# C2000_communications_dock.net
KiCad netlist of a schematic drawn in EAGLE
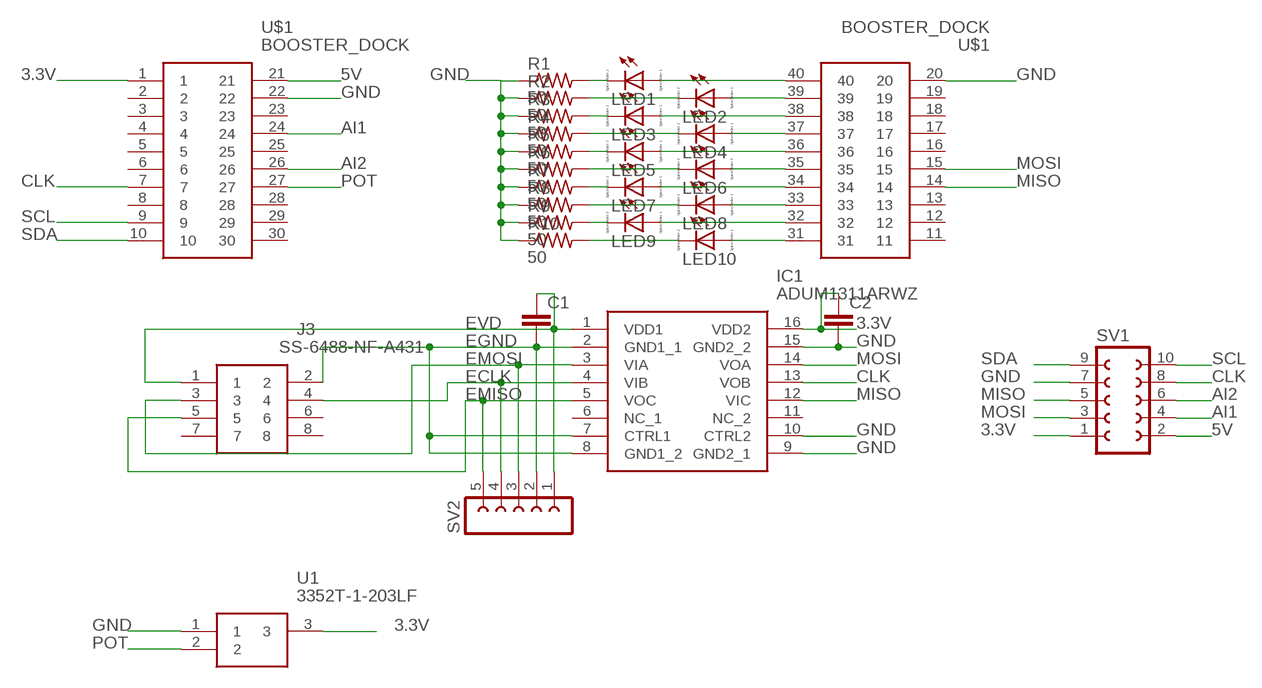
[diagram p0: schematic, sheet 1]

(export (version "E")
  (design (tool "Eeschema 10.0.6"))
  (components
    (comp (ref "C1")
      (value "C-EUC0603")
      (footprint "eagle-import:C0603")
      (libsource (lib "eagle-import") (part "C-EUC0603"))
    )
    (comp (ref "C2")
      (value "C-EUC0603")
      (footprint "eagle-import:C0603")
      (libsource (lib "eagle-import") (part "C-EUC0603"))
    )
    (comp (ref "IC1")
      (value "ADUM1311ARWZ")
      (footprint "eagle-import:SOIC127P1032X265-16N")
      (fields (field (name "MOUSER_PART_NUMBER") "584-ADUM1311ARWZ"))
      (libsource (lib "eagle-import") (part "ADUM1311ARWZ"))
    )
    (comp (ref "J3")
      (value "SS-6488-NF-A431")
      (footprint "eagle-import:SS6488NFA431")
      (fields (field (name "MOUSER_PART_NUMBER") "530-SS-6488-NF-A431"))
      (libsource (lib "eagle-import") (part "SS-6488-NF-A431"))
    )
    (comp (ref "LED1")
      (value "LED_ESML0603")
      (footprint "eagle-import:LED_SML0603")
      (libsource (lib "eagle-import") (part "LED_ESML0603"))
    )
    (comp (ref "LED2")
      (value "LED_ESML0603")
      (footprint "eagle-import:LED_SML0603")
      (libsource (lib "eagle-import") (part "LED_ESML0603"))
    )
    (comp (ref "LED3")
      (value "LED_ESML0603")
      (footprint "eagle-import:LED_SML0603")
      (libsource (lib "eagle-import") (part "LED_ESML0603"))
    )
    (comp (ref "LED4")
      (value "LED_ESML0603")
      (footprint "eagle-import:LED_SML0603")
      (libsource (lib "eagle-import") (part "LED_ESML0603"))
    )
    (comp (ref "LED5")
      (value "LED_ESML0603")
      (footprint "eagle-import:LED_SML0603")
      (libsource (lib "eagle-import") (part "LED_ESML0603"))
    )
    (comp (ref "LED6")
      (value "LED_ESML0603")
      (footprint "eagle-import:LED_SML0603")
      (libsource (lib "eagle-import") (part "LED_ESML0603"))
    )
    (comp (ref "LED7")
      (value "LED_ESML0603")
      (footprint "eagle-import:LED_SML0603")
      (libsource (lib "eagle-import") (part "LED_ESML0603"))
    )
    (comp (ref "LED8")
      (value "LED_ESML0603")
      (footprint "eagle-import:LED_SML0603")
      (libsource (lib "eagle-import") (part "LED_ESML0603"))
    )
    (comp (ref "LED9")
      (value "LED_ESML0603")
      (footprint "eagle-import:LED_SML0603")
      (libsource (lib "eagle-import") (part "LED_ESML0603"))
    )
    (comp (ref "LED10")
      (value "LED_ESML0603")
      (footprint "eagle-import:LED_SML0603")
      (libsource (lib "eagle-import") (part "LED_ESML0603"))
    )
    (comp (ref "R1")
      (value "50")
      (footprint "eagle-import:R0603")
      (libsource (lib "eagle-import") (part "R-US_R0603"))
    )
    (comp (ref "R2")
      (value "50")
      (footprint "eagle-import:R0603")
      (libsource (lib "eagle-import") (part "R-US_R0603"))
    )
    (comp (ref "R3")
      (value "50")
      (footprint "eagle-import:R0603")
      (libsource (lib "eagle-import") (part "R-US_R0603"))
    )
    (comp (ref "R4")
      (value "50")
      (footprint "eagle-import:R0603")
      (libsource (lib "eagle-import") (part "R-US_R0603"))
    )
    (comp (ref "R5")
      (value "50")
      (footprint "eagle-import:R0603")
      (libsource (lib "eagle-import") (part "R-US_R0603"))
    )
    (comp (ref "R6")
      (value "50")
      (footprint "eagle-import:R0603")
      (libsource (lib "eagle-import") (part "R-US_R0603"))
    )
    (comp (ref "R7")
      (value "50")
      (footprint "eagle-import:R0603")
      (libsource (lib "eagle-import") (part "R-US_R0603"))
    )
    (comp (ref "R8")
      (value "50")
      (footprint "eagle-import:R0603")
      (libsource (lib "eagle-import") (part "R-US_R0603"))
    )
    (comp (ref "R9")
      (value "50")
      (footprint "eagle-import:R0603")
      (libsource (lib "eagle-import") (part "R-US_R0603"))
    )
    (comp (ref "R10")
      (value "50")
      (footprint "eagle-import:R0603")
      (libsource (lib "eagle-import") (part "R-US_R0603"))
    )
    (comp (ref "SV1")
      (value "FE05-2")
      (footprint "eagle-import:FE05-2")
      (libsource (lib "eagle-import") (part "FE05-2"))
    )
    (comp (ref "SV2")
      (value "FE05-1")
      (footprint "eagle-import:FE05-1")
      (libsource (lib "eagle-import") (part "FE05-1"))
    )
    (comp (ref "U$1")
      (value "BOOSTER_DOCK")
      (footprint "eagle-import:BOOSTER_DOCK")
      (libsource (lib "eagle-import") (part "BOOSTER_DOCK"))
    )
    (comp (ref "U1")
      (value "3352T-1-203LF")
      (footprint "eagle-import:3352T-1-203LF")
      (fields (field (name "MOUSER_PART_NUMBER") "652-3352T-1-203LF"))
      (libsource (lib "eagle-import") (part "3352T-1-203LF"))
    )
  )
  (nets
    (net (code "1") (name "/3.3V") (class "Default")
      (node (ref "C2") (pin "1") (pinfunction "1_1") (pintype "passive"))
      (node (ref "IC1") (pin "16") (pinfunction "VDD2_16") (pintype "bidirectional"))
      (node (ref "SV1") (pin "1") (pinfunction "1_1") (pintype "passive"))
      (node (ref "U$1") (pin "1") (pinfunction "1_1") (pintype "bidirectional"))
      (node (ref "U1") (pin "3") (pinfunction "3_3") (pintype "bidirectional"))
    )
    (net (code "2") (name "/5V") (class "Default")
      (node (ref "SV1") (pin "2") (pinfunction "2_2") (pintype "passive"))
      (node (ref "U$1") (pin "21") (pinfunction "21_21") (pintype "bidirectional"))
    )
    (net (code "3") (name "/AI1") (class "Default")
      (node (ref "SV1") (pin "4") (pinfunction "4_4") (pintype "passive"))
      (node (ref "U$1") (pin "24") (pinfunction "24_24") (pintype "bidirectional"))
    )
    (net (code "4") (name "/AI2") (class "Default")
      (node (ref "SV1") (pin "6") (pinfunction "6_6") (pintype "passive"))
      (node (ref "U$1") (pin "26") (pinfunction "26_26") (pintype "bidirectional"))
    )
    (net (code "5") (name "/CLK") (class "Default")
      (node (ref "IC1") (pin "13") (pinfunction "VOB_13") (pintype "bidirectional"))
      (node (ref "SV1") (pin "8") (pinfunction "8_8") (pintype "passive"))
      (node (ref "U$1") (pin "7") (pinfunction "7_7") (pintype "bidirectional"))
    )
    (net (code "6") (name "/ECLK") (class "Default")
      (node (ref "IC1") (pin "4") (pinfunction "VIB_4") (pintype "bidirectional"))
      (node (ref "J3") (pin "4") (pinfunction "4_4") (pintype "bidirectional"))
      (node (ref "SV2") (pin "4") (pinfunction "4_4") (pintype "passive"))
    )
    (net (code "7") (name "/EGND") (class "Default")
      (node (ref "C1") (pin "2") (pinfunction "2_2") (pintype "passive"))
      (node (ref "IC1") (pin "2") (pinfunction "GND1_1_2") (pintype "bidirectional"))
      (node (ref "IC1") (pin "7") (pinfunction "CTRL1_7") (pintype "bidirectional"))
      (node (ref "IC1") (pin "8") (pinfunction "GND1_2_8") (pintype "bidirectional"))
      (node (ref "J3") (pin "2") (pinfunction "2_2") (pintype "bidirectional"))
      (node (ref "SV2") (pin "2") (pinfunction "2_2") (pintype "passive"))
    )
    (net (code "8") (name "/EMISO") (class "Default")
      (node (ref "IC1") (pin "5") (pinfunction "VOC_5") (pintype "bidirectional"))
      (node (ref "J3") (pin "5") (pinfunction "5_5") (pintype "bidirectional"))
      (node (ref "SV2") (pin "5") (pinfunction "5_5") (pintype "passive"))
    )
    (net (code "9") (name "/EMOSI") (class "Default")
      (node (ref "IC1") (pin "3") (pinfunction "VIA_3") (pintype "bidirectional"))
      (node (ref "J3") (pin "3") (pinfunction "3_3") (pintype "bidirectional"))
      (node (ref "SV2") (pin "3") (pinfunction "3_3") (pintype "passive"))
    )
    (net (code "10") (name "/EVD") (class "Default")
      (node (ref "C1") (pin "1") (pinfunction "1_1") (pintype "passive"))
      (node (ref "IC1") (pin "1") (pinfunction "VDD1_1") (pintype "bidirectional"))
      (node (ref "J3") (pin "1") (pinfunction "1_1") (pintype "bidirectional"))
      (node (ref "SV2") (pin "1") (pinfunction "1_1") (pintype "passive"))
    )
    (net (code "11") (name "/GND") (class "Default")
      (node (ref "C2") (pin "2") (pinfunction "2_2") (pintype "passive"))
      (node (ref "IC1") (pin "10") (pinfunction "CTRL2_10") (pintype "bidirectional"))
      (node (ref "IC1") (pin "15") (pinfunction "GND2_2_15") (pintype "bidirectional"))
      (node (ref "IC1") (pin "9") (pinfunction "GND2_1_9") (pintype "bidirectional"))
      (node (ref "R1") (pin "1") (pinfunction "1_1") (pintype "passive"))
      (node (ref "R10") (pin "1") (pinfunction "1_1") (pintype "passive"))
      (node (ref "R2") (pin "1") (pinfunction "1_1") (pintype "passive"))
      (node (ref "R3") (pin "1") (pinfunction "1_1") (pintype "passive"))
      (node (ref "R4") (pin "1") (pinfunction "1_1") (pintype "passive"))
      (node (ref "R5") (pin "1") (pinfunction "1_1") (pintype "passive"))
      (node (ref "R6") (pin "1") (pinfunction "1_1") (pintype "passive"))
      (node (ref "R7") (pin "1") (pinfunction "1_1") (pintype "passive"))
      (node (ref "R8") (pin "1") (pinfunction "1_1") (pintype "passive"))
      (node (ref "R9") (pin "1") (pinfunction "1_1") (pintype "passive"))
      (node (ref "SV1") (pin "7") (pinfunction "7_7") (pintype "passive"))
      (node (ref "U$1") (pin "20") (pinfunction "20_20") (pintype "bidirectional"))
      (node (ref "U$1") (pin "22") (pinfunction "22_22") (pintype "bidirectional"))
      (node (ref "U1") (pin "1") (pinfunction "1_1") (pintype "bidirectional"))
    )
    (net (code "12") (name "/MISO") (class "Default")
      (node (ref "IC1") (pin "12") (pinfunction "VIC_12") (pintype "bidirectional"))
      (node (ref "SV1") (pin "5") (pinfunction "5_5") (pintype "passive"))
      (node (ref "U$1") (pin "14") (pinfunction "14_14") (pintype "bidirectional"))
    )
    (net (code "13") (name "/MOSI") (class "Default")
      (node (ref "IC1") (pin "14") (pinfunction "VOA_14") (pintype "bidirectional"))
      (node (ref "SV1") (pin "3") (pinfunction "3_3") (pintype "passive"))
      (node (ref "U$1") (pin "15") (pinfunction "15_15") (pintype "bidirectional"))
    )
    (net (code "14") (name "/POT") (class "Default")
      (node (ref "U$1") (pin "27") (pinfunction "27_27") (pintype "bidirectional"))
      (node (ref "U1") (pin "2") (pinfunction "2_2") (pintype "bidirectional"))
    )
    (net (code "15") (name "/SCL") (class "Default")
      (node (ref "SV1") (pin "10") (pinfunction "10_10") (pintype "passive"))
      (node (ref "U$1") (pin "9") (pinfunction "9_9") (pintype "bidirectional"))
    )
    (net (code "16") (name "/SDA") (class "Default")
      (node (ref "SV1") (pin "9") (pinfunction "9_9") (pintype "passive"))
      (node (ref "U$1") (pin "10") (pinfunction "10_10") (pintype "bidirectional"))
    )
    (net (code "17") (name "Net-(LED1-PadA)") (class "Default")
      (node (ref "LED1") (pin "A") (pinfunction "A_A") (pintype "passive"))
      (node (ref "U$1") (pin "40") (pinfunction "40_40") (pintype "bidirectional"))
    )
    (net (code "18") (name "Net-(LED1-PadC)") (class "Default")
      (node (ref "LED1") (pin "C") (pinfunction "C_C") (pintype "passive"))
      (node (ref "R1") (pin "2") (pinfunction "2_2") (pintype "passive"))
    )
    (net (code "19") (name "Net-(LED2-PadA)") (class "Default")
      (node (ref "LED2") (pin "A") (pinfunction "A_A") (pintype "passive"))
      (node (ref "U$1") (pin "39") (pinfunction "39_39") (pintype "bidirectional"))
    )
    (net (code "20") (name "Net-(LED2-PadC)") (class "Default")
      (node (ref "LED2") (pin "C") (pinfunction "C_C") (pintype "passive"))
      (node (ref "R2") (pin "2") (pinfunction "2_2") (pintype "passive"))
    )
    (net (code "21") (name "Net-(LED3-PadA)") (class "Default")
      (node (ref "LED3") (pin "A") (pinfunction "A_A") (pintype "passive"))
      (node (ref "U$1") (pin "38") (pinfunction "38_38") (pintype "bidirectional"))
    )
    (net (code "22") (name "Net-(LED3-PadC)") (class "Default")
      (node (ref "LED3") (pin "C") (pinfunction "C_C") (pintype "passive"))
      (node (ref "R3") (pin "2") (pinfunction "2_2") (pintype "passive"))
    )
    (net (code "23") (name "Net-(LED4-PadA)") (class "Default")
      (node (ref "LED4") (pin "A") (pinfunction "A_A") (pintype "passive"))
      (node (ref "U$1") (pin "37") (pinfunction "37_37") (pintype "bidirectional"))
    )
    (net (code "24") (name "Net-(LED4-PadC)") (class "Default")
      (node (ref "LED4") (pin "C") (pinfunction "C_C") (pintype "passive"))
      (node (ref "R4") (pin "2") (pinfunction "2_2") (pintype "passive"))
    )
    (net (code "25") (name "Net-(LED5-PadA)") (class "Default")
      (node (ref "LED5") (pin "A") (pinfunction "A_A") (pintype "passive"))
      (node (ref "U$1") (pin "36") (pinfunction "36_36") (pintype "bidirectional"))
    )
    (net (code "26") (name "Net-(LED5-PadC)") (class "Default")
      (node (ref "LED5") (pin "C") (pinfunction "C_C") (pintype "passive"))
      (node (ref "R5") (pin "2") (pinfunction "2_2") (pintype "passive"))
    )
    (net (code "27") (name "Net-(LED6-PadA)") (class "Default")
      (node (ref "LED6") (pin "A") (pinfunction "A_A") (pintype "passive"))
      (node (ref "U$1") (pin "35") (pinfunction "35_35") (pintype "bidirectional"))
    )
    (net (code "28") (name "Net-(LED6-PadC)") (class "Default")
      (node (ref "LED6") (pin "C") (pinfunction "C_C") (pintype "passive"))
      (node (ref "R6") (pin "2") (pinfunction "2_2") (pintype "passive"))
    )
    (net (code "29") (name "Net-(LED7-PadA)") (class "Default")
      (node (ref "LED7") (pin "A") (pinfunction "A_A") (pintype "passive"))
      (node (ref "U$1") (pin "34") (pinfunction "34_34") (pintype "bidirectional"))
    )
    (net (code "30") (name "Net-(LED7-PadC)") (class "Default")
      (node (ref "LED7") (pin "C") (pinfunction "C_C") (pintype "passive"))
      (node (ref "R7") (pin "2") (pinfunction "2_2") (pintype "passive"))
    )
    (net (code "31") (name "Net-(LED8-PadA)") (class "Default")
      (node (ref "LED8") (pin "A") (pinfunction "A_A") (pintype "passive"))
      (node (ref "U$1") (pin "33") (pinfunction "33_33") (pintype "bidirectional"))
    )
    (net (code "32") (name "Net-(LED8-PadC)") (class "Default")
      (node (ref "LED8") (pin "C") (pinfunction "C_C") (pintype "passive"))
      (node (ref "R8") (pin "2") (pinfunction "2_2") (pintype "passive"))
    )
    (net (code "33") (name "Net-(LED9-PadA)") (class "Default")
      (node (ref "LED9") (pin "A") (pinfunction "A_A") (pintype "passive"))
      (node (ref "U$1") (pin "32") (pinfunction "32_32") (pintype "bidirectional"))
    )
    (net (code "34") (name "Net-(LED9-PadC)") (class "Default")
      (node (ref "LED9") (pin "C") (pinfunction "C_C") (pintype "passive"))
      (node (ref "R9") (pin "2") (pinfunction "2_2") (pintype "passive"))
    )
    (net (code "35") (name "Net-(LED10-PadA)") (class "Default")
      (node (ref "LED10") (pin "A") (pinfunction "A_A") (pintype "passive"))
      (node (ref "U$1") (pin "31") (pinfunction "31_31") (pintype "bidirectional"))
    )
    (net (code "36") (name "Net-(LED10-PadC)") (class "Default")
      (node (ref "LED10") (pin "C") (pinfunction "C_C") (pintype "passive"))
      (node (ref "R10") (pin "2") (pinfunction "2_2") (pintype "passive"))
    )
    (net (code "37") (name "unconnected-(IC1-NC_1-Pad6)") (class "Default")
      (node (ref "IC1") (pin "6") (pinfunction "NC_1_6") (pintype "bidirectional"))
    )
    (net (code "38") (name "unconnected-(IC1-NC_2-Pad11)") (class "Default")
      (node (ref "IC1") (pin "11") (pinfunction "NC_2_11") (pintype "bidirectional"))
    )
    (net (code "39") (name "unconnected-(J3-Pad6)") (class "Default")
      (node (ref "J3") (pin "6") (pinfunction "6_6") (pintype "bidirectional"))
    )
    (net (code "40") (name "unconnected-(J3-Pad7)") (class "Default")
      (node (ref "J3") (pin "7") (pinfunction "7_7") (pintype "bidirectional"))
    )
    (net (code "41") (name "unconnected-(J3-Pad8)") (class "Default")
      (node (ref "J3") (pin "8") (pinfunction "8_8") (pintype "bidirectional"))
    )
    (net (code "42") (name "unconnected-(U$1-Pad2)") (class "Default")
      (node (ref "U$1") (pin "2") (pinfunction "2_2") (pintype "bidirectional"))
    )
    (net (code "43") (name "unconnected-(U$1-Pad3)") (class "Default")
      (node (ref "U$1") (pin "3") (pinfunction "3_3") (pintype "bidirectional"))
    )
    (net (code "44") (name "unconnected-(U$1-Pad4)") (class "Default")
      (node (ref "U$1") (pin "4") (pinfunction "4_4") (pintype "bidirectional"))
    )
    (net (code "45") (name "unconnected-(U$1-Pad5)") (class "Default")
      (node (ref "U$1") (pin "5") (pinfunction "5_5") (pintype "bidirectional"))
    )
    (net (code "46") (name "unconnected-(U$1-Pad6)") (class "Default")
      (node (ref "U$1") (pin "6") (pinfunction "6_6") (pintype "bidirectional"))
    )
    (net (code "47") (name "unconnected-(U$1-Pad8)") (class "Default")
      (node (ref "U$1") (pin "8") (pinfunction "8_8") (pintype "bidirectional"))
    )
    (net (code "48") (name "unconnected-(U$1-Pad11)") (class "Default")
      (node (ref "U$1") (pin "11") (pinfunction "11_11") (pintype "bidirectional"))
    )
    (net (code "49") (name "unconnected-(U$1-Pad12)") (class "Default")
      (node (ref "U$1") (pin "12") (pinfunction "12_12") (pintype "bidirectional"))
    )
    (net (code "50") (name "unconnected-(U$1-Pad13)") (class "Default")
      (node (ref "U$1") (pin "13") (pinfunction "13_13") (pintype "bidirectional"))
    )
    (net (code "51") (name "unconnected-(U$1-Pad16)") (class "Default")
      (node (ref "U$1") (pin "16") (pinfunction "16_16") (pintype "bidirectional"))
    )
    (net (code "52") (name "unconnected-(U$1-Pad17)") (class "Default")
      (node (ref "U$1") (pin "17") (pinfunction "17_17") (pintype "bidirectional"))
    )
    (net (code "53") (name "unconnected-(U$1-Pad18)") (class "Default")
      (node (ref "U$1") (pin "18") (pinfunction "18_18") (pintype "bidirectional"))
    )
    (net (code "54") (name "unconnected-(U$1-Pad19)") (class "Default")
      (node (ref "U$1") (pin "19") (pinfunction "19_19") (pintype "bidirectional"))
    )
    (net (code "55") (name "unconnected-(U$1-Pad23)") (class "Default")
      (node (ref "U$1") (pin "23") (pinfunction "23_23") (pintype "bidirectional"))
    )
    (net (code "56") (name "unconnected-(U$1-Pad25)") (class "Default")
      (node (ref "U$1") (pin "25") (pinfunction "25_25") (pintype "bidirectional"))
    )
    (net (code "57") (name "unconnected-(U$1-Pad28)") (class "Default")
      (node (ref "U$1") (pin "28") (pinfunction "28_28") (pintype "bidirectional"))
    )
    (net (code "58") (name "unconnected-(U$1-Pad29)") (class "Default")
      (node (ref "U$1") (pin "29") (pinfunction "29_29") (pintype "bidirectional"))
    )
    (net (code "59") (name "unconnected-(U$1-Pad30)") (class "Default")
      (node (ref "U$1") (pin "30") (pinfunction "30_30") (pintype "bidirectional"))
    )
  )
)
